# Headphone-Amplifier-ClassAB-alt5.net
KiCad netlist of a schematic drawn in EAGLE
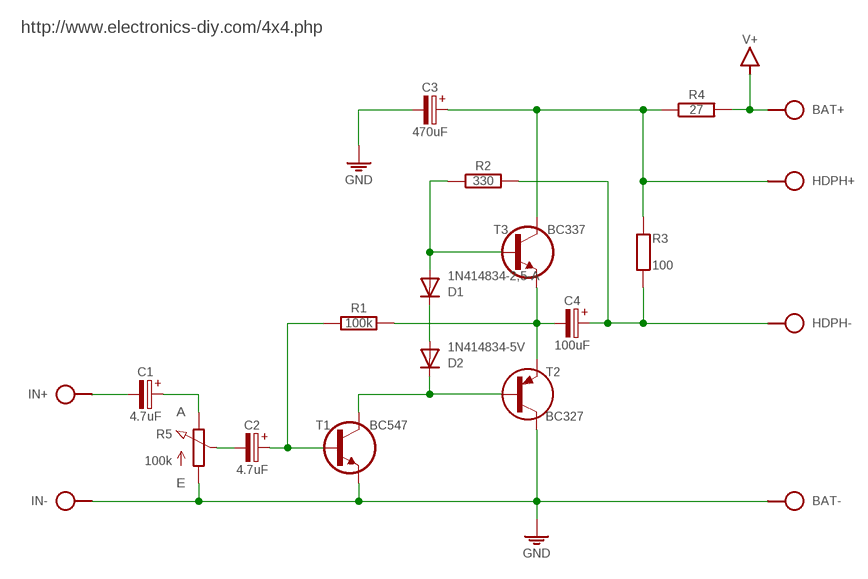
[diagram p0: schematic, sheet 1]

(export (version "E")
  (design (tool "Eeschema 10.0.6"))
  (components
    (comp (ref "BAT")
      (value "SPAD+-+-")
      (footprint "eagle-import:SPAD+-")
      (libsource (lib "eagle-import") (part "SPAD+-+-"))
    )
    (comp (ref "C1")
      (value "4.7uF")
      (footprint "eagle-import:E2.5-4_V")
      (libsource (lib "eagle-import") (part "CPOLE2,5-4/V"))
    )
    (comp (ref "C2")
      (value "4.7uF")
      (footprint "eagle-import:E2.5-4_V")
      (libsource (lib "eagle-import") (part "CPOLE2,5-4/V"))
    )
    (comp (ref "C3")
      (value "470uF")
      (footprint "eagle-import:E2,5-5_V")
      (libsource (lib "eagle-import") (part "CPOLE2,5-5/V"))
    )
    (comp (ref "C4")
      (value "100uF")
      (footprint "eagle-import:E2.5-4_V")
      (libsource (lib "eagle-import") (part "CPOLE2,5-4/V"))
    )
    (comp (ref "D1")
      (value "1N414834-2,5-A")
      (footprint "eagle-import:DO34-2,5-A")
      (libsource (lib "eagle-import") (part "1N414834-2,5-A"))
    )
    (comp (ref "D2")
      (value "1N414834-5V")
      (footprint "eagle-import:DO34-5V")
      (libsource (lib "eagle-import") (part "1N414834-5V"))
    )
    (comp (ref "HDPH")
      (value "SPAD+-+-")
      (footprint "eagle-import:SPAD+-")
      (libsource (lib "eagle-import") (part "SPAD+-+-"))
    )
    (comp (ref "IN")
      (value "SPAD+--+")
      (footprint "eagle-import:SPAD-+")
      (libsource (lib "eagle-import") (part "SPAD+--+"))
    )
    (comp (ref "R1")
      (value "100k")
      (footprint "eagle-import:0202_2")
      (libsource (lib "eagle-import") (part "R-H0202/2"))
    )
    (comp (ref "R2")
      (value "330")
      (footprint "eagle-import:0202_2V")
      (libsource (lib "eagle-import") (part "R-H0202/2V"))
    )
    (comp (ref "R3")
      (value "100")
      (footprint "eagle-import:0202_2")
      (libsource (lib "eagle-import") (part "R0202/2"))
    )
    (comp (ref "R4")
      (value "27")
      (footprint "eagle-import:0204_2.54")
      (libsource (lib "eagle-import") (part "R-H0204/2.54"))
    )
    (comp (ref "R5")
      (value "100k")
      (footprint "eagle-import:CONN-3P")
      (libsource (lib "eagle-import") (part "POT-3P"))
    )
    (comp (ref "T1")
      (value "BC547")
      (footprint "eagle-import:TO92-CBE")
      (libsource (lib "eagle-import") (part "BC547CBE"))
    )
    (comp (ref "T2")
      (value "BC327")
      (footprint "eagle-import:TO92")
      (libsource (lib "eagle-import") (part "BC327"))
    )
    (comp (ref "T3")
      (value "BC337")
      (footprint "eagle-import:TO92-CBE")
      (libsource (lib "eagle-import") (part "BC337CBE"))
    )
  )
  (nets
    (net (code "1") (name "GND") (class "Default")
      (node (ref "BAT") (pin "1") (pinfunction "P$1_1") (pintype "passive"))
      (node (ref "C3") (pin "-") (pinfunction "-_-") (pintype "passive"))
      (node (ref "IN") (pin "1") (pinfunction "P$1_1") (pintype "passive"))
      (node (ref "R5") (pin "1") (pinfunction "A_1") (pintype "passive"))
      (node (ref "T1") (pin "E") (pinfunction "E_E") (pintype "passive"))
      (node (ref "T2") (pin "1") (pinfunction "C_1") (pintype "passive"))
    )
    (net (code "2") (name "Net-(C2-Pad+)") (class "Default")
      (node (ref "C2") (pin "+") (pinfunction "+_+") (pintype "passive"))
      (node (ref "R1") (pin "1") (pinfunction "1_1") (pintype "passive"))
      (node (ref "T1") (pin "B") (pinfunction "B_B") (pintype "passive"))
    )
    (net (code "3") (name "Net-(D1-PadA)") (class "Default")
      (node (ref "D1") (pin "A") (pinfunction "A_A") (pintype "passive"))
      (node (ref "R2") (pin "1") (pinfunction "1_1") (pintype "passive"))
      (node (ref "T3") (pin "B") (pinfunction "B_B") (pintype "passive"))
    )
    (net (code "4") (name "Net-(D1-PadC)") (class "Default")
      (node (ref "D1") (pin "C") (pinfunction "C_C") (pintype "passive"))
      (node (ref "D2") (pin "A") (pinfunction "A_A") (pintype "passive"))
    )
    (net (code "5") (name "Net-(HDPHA-P$1)") (class "Default")
      (node (ref "C3") (pin "+") (pinfunction "+_+") (pintype "passive"))
      (node (ref "HDPH") (pin "2") (pinfunction "P$1_2") (pintype "passive"))
      (node (ref "R3") (pin "1") (pinfunction "1_1") (pintype "passive"))
      (node (ref "R4") (pin "1") (pinfunction "1_1") (pintype "passive"))
      (node (ref "T3") (pin "C") (pinfunction "C_C") (pintype "passive"))
    )
    (net (code "6") (name "Net-(HDPHB-P$1)") (class "Default")
      (node (ref "C4") (pin "+") (pinfunction "+_+") (pintype "passive"))
      (node (ref "HDPH") (pin "1") (pinfunction "P$1_1") (pintype "passive"))
      (node (ref "R2") (pin "2") (pinfunction "2_2") (pintype "passive"))
      (node (ref "R3") (pin "2") (pinfunction "2_2") (pintype "passive"))
    )
    (net (code "7") (name "Net-(INA-P$1)") (class "Default")
      (node (ref "C1") (pin "-") (pinfunction "-_-") (pintype "passive"))
      (node (ref "IN") (pin "2") (pinfunction "P$1_2") (pintype "passive"))
    )
    (net (code "8") (name "Net-(R5-E)") (class "Default")
      (node (ref "C1") (pin "+") (pinfunction "+_+") (pintype "passive"))
      (node (ref "R5") (pin "3") (pinfunction "E_3") (pintype "passive"))
    )
    (net (code "9") (name "Net-(R5-S)") (class "Default")
      (node (ref "C2") (pin "-") (pinfunction "-_-") (pintype "passive"))
      (node (ref "R5") (pin "2") (pinfunction "S_2") (pintype "passive"))
    )
    (net (code "10") (name "Net-(T2-B)") (class "Default")
      (node (ref "D2") (pin "C") (pinfunction "C_C") (pintype "passive"))
      (node (ref "T1") (pin "C") (pinfunction "C_C") (pintype "passive"))
      (node (ref "T2") (pin "2") (pinfunction "B_2") (pintype "passive"))
    )
    (net (code "11") (name "Net-(T2-E)") (class "Default")
      (node (ref "C4") (pin "-") (pinfunction "-_-") (pintype "passive"))
      (node (ref "R1") (pin "2") (pinfunction "2_2") (pintype "passive"))
      (node (ref "T2") (pin "3") (pinfunction "E_3") (pintype "passive"))
      (node (ref "T3") (pin "E") (pinfunction "E_E") (pintype "passive"))
    )
    (net (code "12") (name "V+") (class "Default")
      (node (ref "BAT") (pin "2") (pinfunction "P$1_2") (pintype "passive"))
      (node (ref "R4") (pin "2") (pinfunction "2_2") (pintype "passive"))
    )
  )
)
